# Encoder.net
KiCad netlist of a schematic drawn in Altium Designer
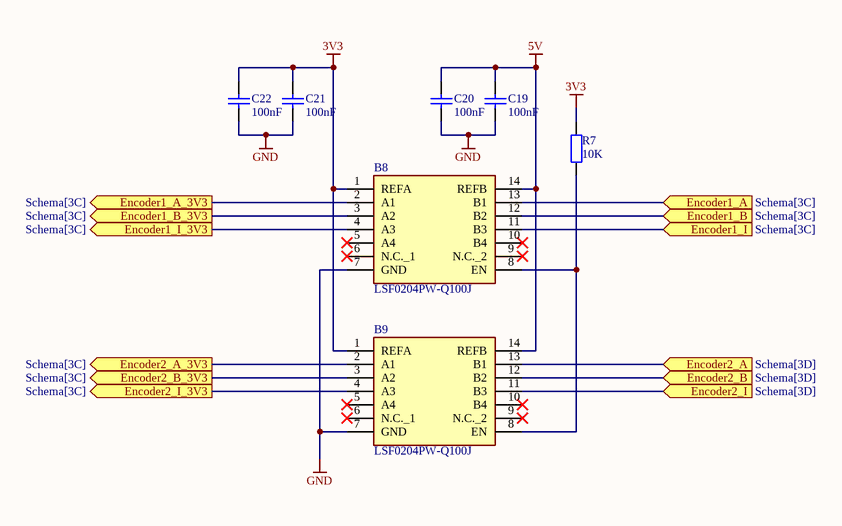
[diagram p0: Encoder.SchDoc]

(export (version "E")
  (design (tool "Eeschema 10.0.6"))
  (components
    (comp (ref "B8")
      (value "LSF0204PW-Q100J")
      (footprint "SOP65P640X110-14M")
      (description "Translation - Voltage Levels ANALOG & LOGIC ICS")
      (fields (field (name "MOUSER PART NUMBER") "771-LSF0204PW-Q100J"))
      (libsource (lib "SchematicLib") (part "LSF0204PW-Q100J"))
    )
    (comp (ref "B9")
      (value "LSF0204PW-Q100J")
      (footprint "SOP65P640X110-14M")
      (description "Translation - Voltage Levels ANALOG & LOGIC ICS")
      (fields (field (name "MOUSER PART NUMBER") "771-LSF0204PW-Q100J"))
      (libsource (lib "SchematicLib") (part "LSF0204PW-Q100J"))
    )
    (comp (ref "C19")
      (value "100nF")
      (footprint "0805_Lorin")
      (description "Capacitor")
      (fields (field (name "Comment") "Cap") (field (name "PUBLISHER") "Altium Limited"))
      (libsource (lib "Miscellaneous Devices") (part "Cap"))
    )
    (comp (ref "C20")
      (value "100nF")
      (footprint "0805_Lorin")
      (description "Capacitor")
      (fields (field (name "Comment") "Cap") (field (name "PUBLISHER") "Altium Limited"))
      (libsource (lib "Miscellaneous Devices") (part "Cap"))
    )
    (comp (ref "C21")
      (value "100nF")
      (footprint "0805_Lorin")
      (description "Capacitor")
      (fields (field (name "Comment") "Cap") (field (name "PUBLISHER") "Altium Limited"))
      (libsource (lib "Miscellaneous Devices") (part "Cap"))
    )
    (comp (ref "C22")
      (value "100nF")
      (footprint "0805_Lorin")
      (description "Capacitor")
      (fields (field (name "Comment") "Cap") (field (name "PUBLISHER") "Altium Limited"))
      (libsource (lib "Miscellaneous Devices") (part "Cap"))
    )
    (comp (ref "R7")
      (value "10K")
      (footprint "0805_Lorin")
      (description "Resistor")
      (fields (field (name "Comment") "Res2") (field (name "PUBLISHER") "Altium Limited"))
      (libsource (lib "Miscellaneous Devices") (part "Res2"))
    )
  )
  (nets
    (net (code "1") (name "/Encoder1_A") (class "Default")
      (node (ref "B8") (pin "13") (pinfunction "B1_13") (pintype "passive"))
    )
    (net (code "2") (name "/Encoder1_A_3V3") (class "Default")
      (node (ref "B8") (pin "2") (pinfunction "A1_2") (pintype "passive"))
    )
    (net (code "3") (name "/Encoder1_B") (class "Default")
      (node (ref "B8") (pin "12") (pinfunction "B2_12") (pintype "passive"))
    )
    (net (code "4") (name "/Encoder1_B_3V3") (class "Default")
      (node (ref "B8") (pin "3") (pinfunction "A2_3") (pintype "passive"))
    )
    (net (code "5") (name "/Encoder1_I") (class "Default")
      (node (ref "B8") (pin "11") (pinfunction "B3_11") (pintype "passive"))
    )
    (net (code "6") (name "/Encoder1_I_3V3") (class "Default")
      (node (ref "B8") (pin "4") (pinfunction "A3_4") (pintype "passive"))
    )
    (net (code "7") (name "/Encoder2_A") (class "Default")
      (node (ref "B9") (pin "13") (pinfunction "B1_13") (pintype "passive"))
    )
    (net (code "8") (name "/Encoder2_A_3V3") (class "Default")
      (node (ref "B9") (pin "2") (pinfunction "A1_2") (pintype "passive"))
    )
    (net (code "9") (name "/Encoder2_B") (class "Default")
      (node (ref "B9") (pin "12") (pinfunction "B2_12") (pintype "passive"))
    )
    (net (code "10") (name "/Encoder2_B_3V3") (class "Default")
      (node (ref "B9") (pin "3") (pinfunction "A2_3") (pintype "passive"))
    )
    (net (code "11") (name "/Encoder2_I") (class "Default")
      (node (ref "B9") (pin "11") (pinfunction "B3_11") (pintype "passive"))
    )
    (net (code "12") (name "/Encoder2_I_3V3") (class "Default")
      (node (ref "B9") (pin "4") (pinfunction "A3_4") (pintype "passive"))
    )
    (net (code "13") (name "3V3") (class "Default")
      (node (ref "B8") (pin "1") (pinfunction "REFA_1") (pintype "passive"))
      (node (ref "B9") (pin "1") (pinfunction "REFA_1") (pintype "passive"))
      (node (ref "C21") (pin "2") (pinfunction "2_2") (pintype "passive"))
      (node (ref "C22") (pin "2") (pinfunction "2_2") (pintype "passive"))
      (node (ref "R7") (pin "2") (pinfunction "2_2") (pintype "passive"))
    )
    (net (code "14") (name "5V") (class "Default")
      (node (ref "B8") (pin "14") (pinfunction "REFB_14") (pintype "passive"))
      (node (ref "B9") (pin "14") (pinfunction "REFB_14") (pintype "passive"))
      (node (ref "C19") (pin "2") (pinfunction "2_2") (pintype "passive"))
      (node (ref "C20") (pin "2") (pinfunction "2_2") (pintype "passive"))
    )
    (net (code "15") (name "GND") (class "Default")
      (node (ref "B8") (pin "7") (pinfunction "GND_7") (pintype "passive"))
      (node (ref "B9") (pin "7") (pinfunction "GND_7") (pintype "passive"))
      (node (ref "C19") (pin "1") (pinfunction "1_1") (pintype "passive"))
      (node (ref "C20") (pin "1") (pinfunction "1_1") (pintype "passive"))
      (node (ref "C21") (pin "1") (pinfunction "1_1") (pintype "passive"))
      (node (ref "C22") (pin "1") (pinfunction "1_1") (pintype "passive"))
    )
    (net (code "16") (name "Net-(B8-EN)") (class "Default")
      (node (ref "B8") (pin "8") (pinfunction "EN_8") (pintype "passive"))
      (node (ref "B9") (pin "8") (pinfunction "EN_8") (pintype "passive"))
      (node (ref "R7") (pin "1") (pinfunction "1_1") (pintype "passive"))
    )
    (net (code "17") (name "unconnected-(B8-A4-Pad5)") (class "Default")
      (node (ref "B8") (pin "5") (pinfunction "A4_5") (pintype "passive+no_connect"))
    )
    (net (code "18") (name "unconnected-(B8-B4-Pad10)") (class "Default")
      (node (ref "B8") (pin "10") (pinfunction "B4_10") (pintype "passive+no_connect"))
    )
    (net (code "19") (name "unconnected-(B8-N.C._1-Pad6)") (class "Default")
      (node (ref "B8") (pin "6") (pinfunction "N.C._1_6") (pintype "passive+no_connect"))
    )
    (net (code "20") (name "unconnected-(B8-N.C._2-Pad9)") (class "Default")
      (node (ref "B8") (pin "9") (pinfunction "N.C._2_9") (pintype "passive+no_connect"))
    )
    (net (code "21") (name "unconnected-(B9-A4-Pad5)") (class "Default")
      (node (ref "B9") (pin "5") (pinfunction "A4_5") (pintype "passive+no_connect"))
    )
    (net (code "22") (name "unconnected-(B9-B4-Pad10)") (class "Default")
      (node (ref "B9") (pin "10") (pinfunction "B4_10") (pintype "passive+no_connect"))
    )
    (net (code "23") (name "unconnected-(B9-N.C._1-Pad6)") (class "Default")
      (node (ref "B9") (pin "6") (pinfunction "N.C._1_6") (pintype "passive+no_connect"))
    )
    (net (code "24") (name "unconnected-(B9-N.C._2-Pad9)") (class "Default")
      (node (ref "B9") (pin "9") (pinfunction "N.C._2_9") (pintype "passive+no_connect"))
    )
  )
)
